# Single_Matrix.net
KiCad netlist of a schematic drawn in Altium Designer
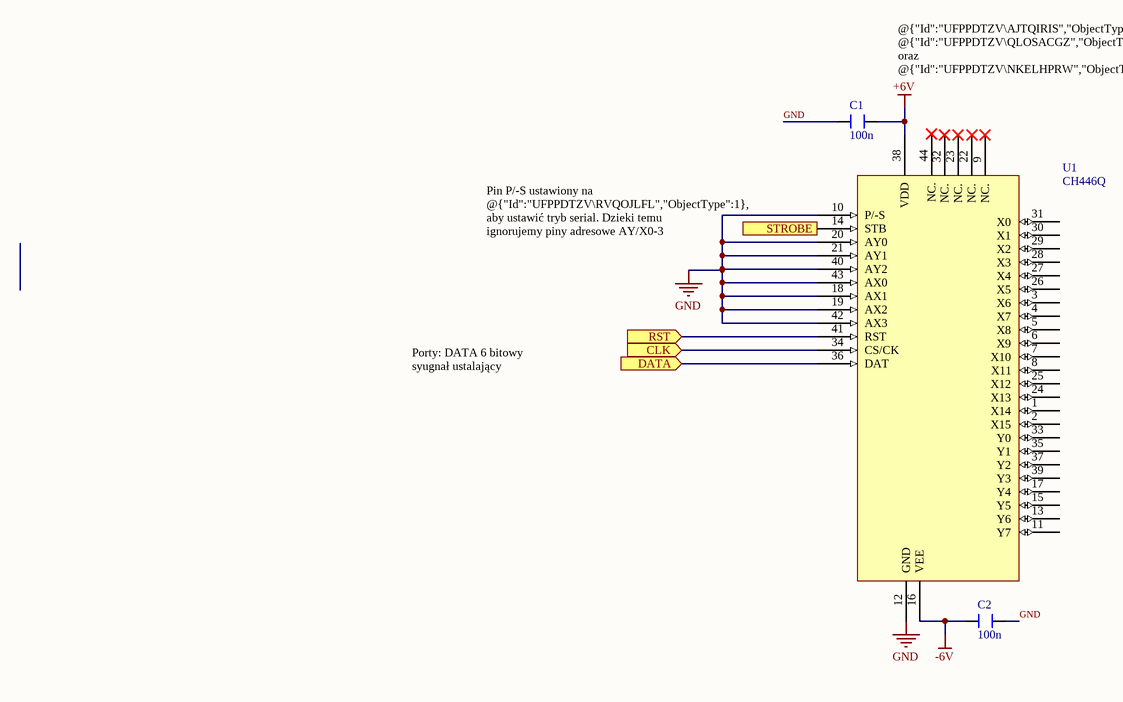
[diagram p0: Single_Matrix.SchDoc]

(export (version "E")
  (design (tool "Eeschema 10.0.6"))
  (components
    (comp (ref "C1")
      (value "100n")
      (footprint "micr_footprints:CL10B104KB8NNNC")
      (description "Capacitor SMD 0603 100n to VDD, VBAT, VDDA, VREF+, VDDUSB, NRST")
      (libsource (lib "unwired_schematic") (part "CL10B104KB8NNNC"))
    )
    (comp (ref "C2")
      (value "100n")
      (footprint "micr_footprints:CL10B104KB8NNNC")
      (description "Capacitor SMD 0603 100n to VDD, VBAT, VDDA, VREF+, VDDUSB, NRST")
      (libsource (lib "unwired_schematic") (part "CL10B104KB8NNNC"))
    )
    (comp (ref "U1")
      (value "CH446Q")
      (footprint "unwired_footprints:LQFP-44_CH446Q")
      (description "Analog Switch Array")
      (libsource (lib "unwired_schematic") (part "CH446Q"))
    )
  )
  (nets
    (net (code "1") (name "+6V") (class "Default")
      (node (ref "C1") (pin "8") (pintype "passive"))
      (node (ref "U1") (pin "38") (pinfunction "VDD_38") (pintype "power_in"))
    )
    (net (code "2") (name "-6V") (class "Default")
      (node (ref "C2") (pin "7") (pintype "passive"))
      (node (ref "U1") (pin "16") (pinfunction "VEE_16") (pintype "power_in"))
    )
    (net (code "3") (name "/CLK") (class "Default")
      (node (ref "U1") (pin "34") (pinfunction "CS/CK_34") (pintype "input"))
    )
    (net (code "4") (name "/DATA") (class "Default")
      (node (ref "U1") (pin "36") (pinfunction "DAT_36") (pintype "input"))
    )
    (net (code "5") (name "/RST") (class "Default")
      (node (ref "U1") (pin "41") (pinfunction "RST_41") (pintype "input"))
    )
    (net (code "6") (name "/STROBE") (class "Default")
      (node (ref "U1") (pin "14") (pinfunction "STB_14") (pintype "input"))
    )
    (net (code "7") (name "GND") (class "Default")
      (node (ref "C1") (pin "7") (pintype "passive"))
      (node (ref "C2") (pin "8") (pintype "passive"))
      (node (ref "U1") (pin "10") (pinfunction "P/-S_10") (pintype "input"))
      (node (ref "U1") (pin "12") (pinfunction "GND_12") (pintype "power_in"))
      (node (ref "U1") (pin "18") (pinfunction "AX1_18") (pintype "input"))
      (node (ref "U1") (pin "19") (pinfunction "AX2_19") (pintype "input"))
      (node (ref "U1") (pin "20") (pinfunction "AY0_20") (pintype "input"))
      (node (ref "U1") (pin "21") (pinfunction "AY1_21") (pintype "input"))
      (node (ref "U1") (pin "40") (pinfunction "AY2_40") (pintype "input"))
      (node (ref "U1") (pin "42") (pinfunction "AX3_42") (pintype "input"))
      (node (ref "U1") (pin "43") (pinfunction "AX0_43") (pintype "input"))
    )
    (net (code "8") (name "unconnected-(U1-NC.-Pad9)") (class "Default")
      (node (ref "U1") (pin "9") (pinfunction "NC._9") (pintype "passive+no_connect"))
    )
    (net (code "9") (name "unconnected-(U1-NC.-Pad22)") (class "Default")
      (node (ref "U1") (pin "22") (pinfunction "NC._22") (pintype "passive"))
    )
    (net (code "10") (name "unconnected-(U1-NC.-Pad23)") (class "Default")
      (node (ref "U1") (pin "23") (pinfunction "NC._23") (pintype "passive+no_connect"))
    )
    (net (code "11") (name "unconnected-(U1-NC.-Pad32)") (class "Default")
      (node (ref "U1") (pin "32") (pinfunction "NC._32") (pintype "passive+no_connect"))
    )
    (net (code "12") (name "unconnected-(U1-NC.-Pad44)") (class "Default")
      (node (ref "U1") (pin "44") (pinfunction "NC._44") (pintype "passive+no_connect"))
    )
    (net (code "13") (name "unconnected-(U1-X0-Pad31)") (class "Default")
      (node (ref "U1") (pin "31") (pinfunction "X0_31") (pintype "bidirectional"))
    )
    (net (code "14") (name "unconnected-(U1-X1-Pad30)") (class "Default")
      (node (ref "U1") (pin "30") (pinfunction "X1_30") (pintype "bidirectional"))
    )
    (net (code "15") (name "unconnected-(U1-X2-Pad29)") (class "Default")
      (node (ref "U1") (pin "29") (pinfunction "X2_29") (pintype "bidirectional"))
    )
    (net (code "16") (name "unconnected-(U1-X3-Pad28)") (class "Default")
      (node (ref "U1") (pin "28") (pinfunction "X3_28") (pintype "bidirectional"))
    )
    (net (code "17") (name "unconnected-(U1-X4-Pad27)") (class "Default")
      (node (ref "U1") (pin "27") (pinfunction "X4_27") (pintype "bidirectional"))
    )
    (net (code "18") (name "unconnected-(U1-X5-Pad26)") (class "Default")
      (node (ref "U1") (pin "26") (pinfunction "X5_26") (pintype "bidirectional"))
    )
    (net (code "19") (name "unconnected-(U1-X6-Pad3)") (class "Default")
      (node (ref "U1") (pin "3") (pinfunction "X6_3") (pintype "bidirectional"))
    )
    (net (code "20") (name "unconnected-(U1-X7-Pad4)") (class "Default")
      (node (ref "U1") (pin "4") (pinfunction "X7_4") (pintype "bidirectional"))
    )
    (net (code "21") (name "unconnected-(U1-X8-Pad5)") (class "Default")
      (node (ref "U1") (pin "5") (pinfunction "X8_5") (pintype "bidirectional"))
    )
    (net (code "22") (name "unconnected-(U1-X9-Pad6)") (class "Default")
      (node (ref "U1") (pin "6") (pinfunction "X9_6") (pintype "bidirectional"))
    )
    (net (code "23") (name "unconnected-(U1-X10-Pad7)") (class "Default")
      (node (ref "U1") (pin "7") (pinfunction "X10_7") (pintype "bidirectional"))
    )
    (net (code "24") (name "unconnected-(U1-X11-Pad8)") (class "Default")
      (node (ref "U1") (pin "8") (pinfunction "X11_8") (pintype "bidirectional"))
    )
    (net (code "25") (name "unconnected-(U1-X12-Pad25)") (class "Default")
      (node (ref "U1") (pin "25") (pinfunction "X12_25") (pintype "bidirectional"))
    )
    (net (code "26") (name "unconnected-(U1-X13-Pad24)") (class "Default")
      (node (ref "U1") (pin "24") (pinfunction "X13_24") (pintype "bidirectional"))
    )
    (net (code "27") (name "unconnected-(U1-X14-Pad1)") (class "Default")
      (node (ref "U1") (pin "1") (pinfunction "X14_1") (pintype "bidirectional"))
    )
    (net (code "28") (name "unconnected-(U1-X15-Pad2)") (class "Default")
      (node (ref "U1") (pin "2") (pinfunction "X15_2") (pintype "bidirectional"))
    )
    (net (code "29") (name "unconnected-(U1-Y0-Pad33)") (class "Default")
      (node (ref "U1") (pin "33") (pinfunction "Y0_33") (pintype "bidirectional"))
    )
    (net (code "30") (name "unconnected-(U1-Y1-Pad35)") (class "Default")
      (node (ref "U1") (pin "35") (pinfunction "Y1_35") (pintype "bidirectional"))
    )
    (net (code "31") (name "unconnected-(U1-Y2-Pad37)") (class "Default")
      (node (ref "U1") (pin "37") (pinfunction "Y2_37") (pintype "bidirectional"))
    )
    (net (code "32") (name "unconnected-(U1-Y3-Pad39)") (class "Default")
      (node (ref "U1") (pin "39") (pinfunction "Y3_39") (pintype "bidirectional"))
    )
    (net (code "33") (name "unconnected-(U1-Y4-Pad17)") (class "Default")
      (node (ref "U1") (pin "17") (pinfunction "Y4_17") (pintype "bidirectional"))
    )
    (net (code "34") (name "unconnected-(U1-Y5-Pad15)") (class "Default")
      (node (ref "U1") (pin "15") (pinfunction "Y5_15") (pintype "bidirectional"))
    )
    (net (code "35") (name "unconnected-(U1-Y6-Pad13)") (class "Default")
      (node (ref "U1") (pin "13") (pinfunction "Y6_13") (pintype "bidirectional"))
    )
    (net (code "36") (name "unconnected-(U1-Y7-Pad11)") (class "Default")
      (node (ref "U1") (pin "11") (pinfunction "Y7_11") (pintype "bidirectional"))
    )
  )
)
